# Main_Design.net
KiCad netlist of a schematic drawn in Altium Designer
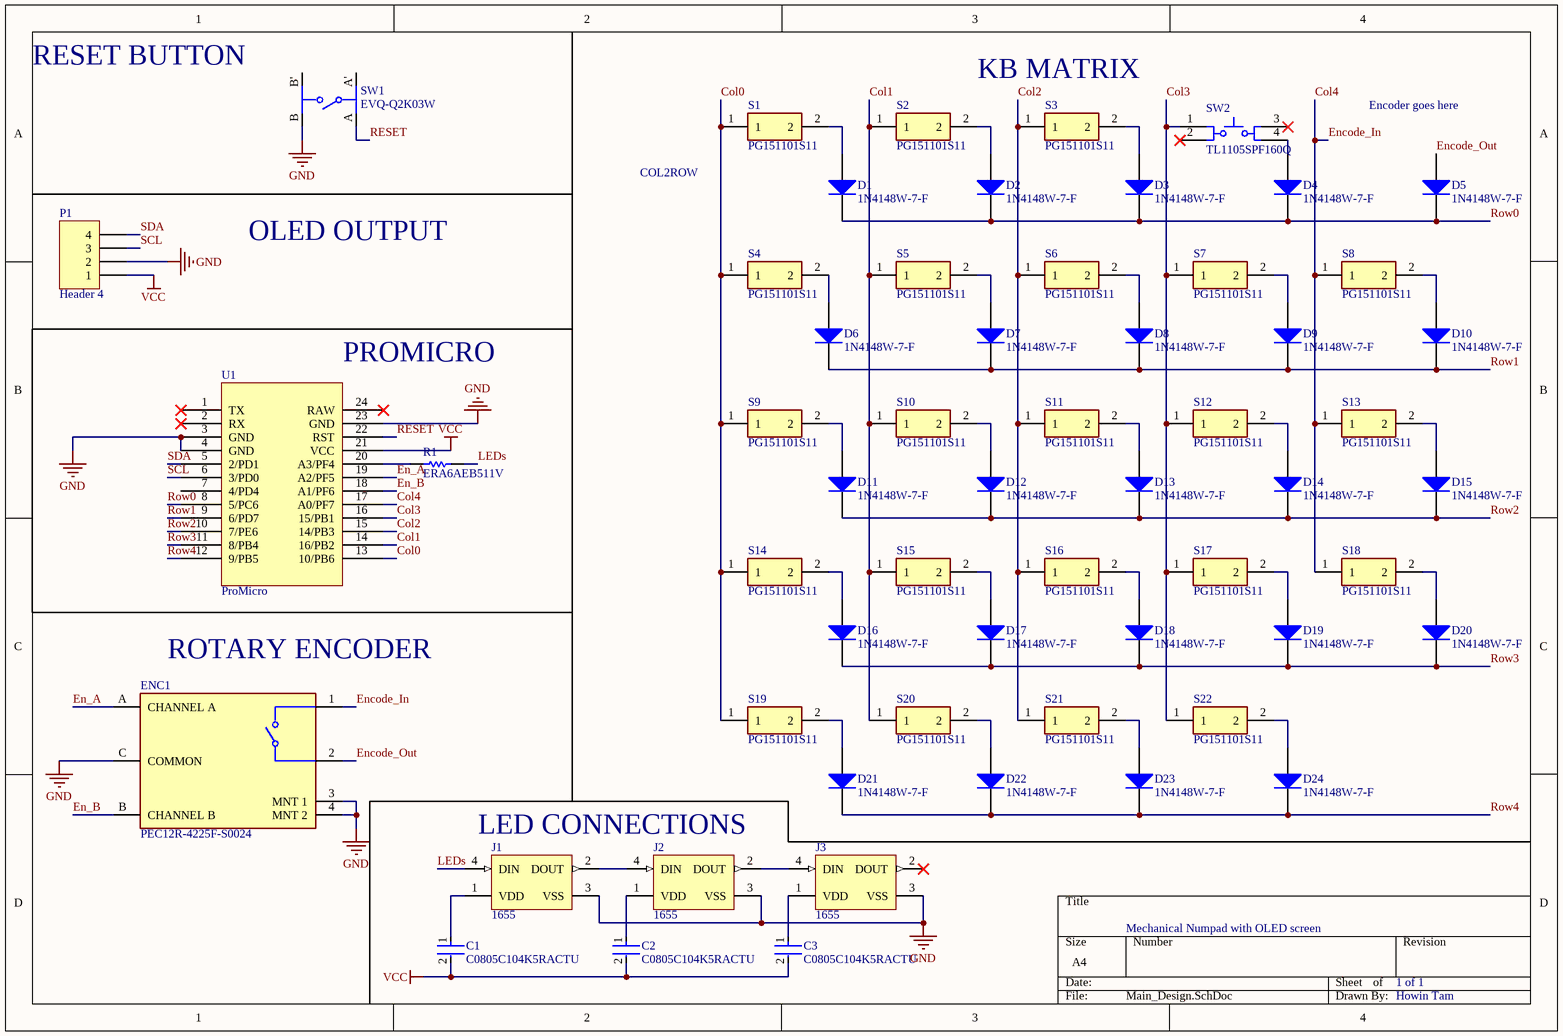
[diagram p0: Main_Design.SchDoc]

(export (version "E")
  (design (tool "Eeschema 10.0.6"))
  (components
    (comp (ref "C1")
      (value "C0805C104K5RACTU")
      (footprint "FP-C0805C-DN-MFG")
      (description "CAP CER 0.1UF 50V X7R 0805")
      (fields
        (field (name "MANUFACTURER") "KEMET")
        (field (name "OCTOPART") "https://octopart.com/c0805c104k5ractu-kemet-143926")
      )
      (libsource (lib "Altium Content Vault") (part "b4654b650e69147ec39a6b967a45e02"))
    )
    (comp (ref "C2")
      (value "C0805C104K5RACTU")
      (footprint "FP-C0805C-DN-MFG")
      (description "CAP CER 0.1UF 50V X7R 0805")
      (fields
        (field (name "MANUFACTURER") "KEMET")
        (field (name "OCTOPART") "https://octopart.com/c0805c104k5ractu-kemet-143926")
      )
      (libsource (lib "Altium Content Vault") (part "b4654b650e69147ec39a6b967a45e02"))
    )
    (comp (ref "C3")
      (value "C0805C104K5RACTU")
      (footprint "FP-C0805C-DN-MFG")
      (description "CAP CER 0.1UF 50V X7R 0805")
      (fields
        (field (name "MANUFACTURER") "KEMET")
        (field (name "OCTOPART") "https://octopart.com/c0805c104k5ractu-kemet-143926")
      )
      (libsource (lib "Altium Content Vault") (part "b4654b650e69147ec39a6b967a45e02"))
    )
    (comp (ref "D1")
      (value "1N4148W-7-F")
      (footprint "DIOD-SOD123-2_V")
      (description "Fast Switching Diode, 100 V, 0.15 A, -65 to 150 degC, 2-Pin?SOD123, RoHS, Tape and Reel")
      (fields (field (name "MANUFACTURER") "DiodesIncorporated"))
      (libsource (lib "Altium Content Vault") (part "D-AK-2"))
    )
    (comp (ref "D2")
      (value "1N4148W-7-F")
      (footprint "DIOD-SOD123-2_V")
      (description "Fast Switching Diode, 100 V, 0.15 A, -65 to 150 degC, 2-Pin?SOD123, RoHS, Tape and Reel")
      (fields (field (name "MANUFACTURER") "DiodesIncorporated"))
      (libsource (lib "Altium Content Vault") (part "D-AK-2"))
    )
    (comp (ref "D3")
      (value "1N4148W-7-F")
      (footprint "DIOD-SOD123-2_V")
      (description "Fast Switching Diode, 100 V, 0.15 A, -65 to 150 degC, 2-Pin?SOD123, RoHS, Tape and Reel")
      (fields (field (name "MANUFACTURER") "DiodesIncorporated"))
      (libsource (lib "Altium Content Vault") (part "D-AK-2"))
    )
    (comp (ref "D4")
      (value "1N4148W-7-F")
      (footprint "DIOD-SOD123-2_V")
      (description "Fast Switching Diode, 100 V, 0.15 A, -65 to 150 degC, 2-Pin?SOD123, RoHS, Tape and Reel")
      (fields (field (name "MANUFACTURER") "DiodesIncorporated"))
      (libsource (lib "Altium Content Vault") (part "D-AK-2"))
    )
    (comp (ref "D5")
      (value "1N4148W-7-F")
      (footprint "DIOD-SOD123-2_V")
      (description "Fast Switching Diode, 100 V, 0.15 A, -65 to 150 degC, 2-Pin?SOD123, RoHS, Tape and Reel")
      (fields (field (name "MANUFACTURER") "DiodesIncorporated"))
      (libsource (lib "Altium Content Vault") (part "D-AK-2"))
    )
    (comp (ref "D6")
      (value "1N4148W-7-F")
      (footprint "DIOD-SOD123-2_V")
      (description "Fast Switching Diode, 100 V, 0.15 A, -65 to 150 degC, 2-Pin?SOD123, RoHS, Tape and Reel")
      (fields (field (name "MANUFACTURER") "DiodesIncorporated"))
      (libsource (lib "Altium Content Vault") (part "D-AK-2"))
    )
    (comp (ref "D7")
      (value "1N4148W-7-F")
      (footprint "DIOD-SOD123-2_V")
      (description "Fast Switching Diode, 100 V, 0.15 A, -65 to 150 degC, 2-Pin?SOD123, RoHS, Tape and Reel")
      (fields (field (name "MANUFACTURER") "DiodesIncorporated"))
      (libsource (lib "Altium Content Vault") (part "D-AK-2"))
    )
    (comp (ref "D8")
      (value "1N4148W-7-F")
      (footprint "DIOD-SOD123-2_V")
      (description "Fast Switching Diode, 100 V, 0.15 A, -65 to 150 degC, 2-Pin?SOD123, RoHS, Tape and Reel")
      (fields (field (name "MANUFACTURER") "DiodesIncorporated"))
      (libsource (lib "Altium Content Vault") (part "D-AK-2"))
    )
    (comp (ref "D9")
      (value "1N4148W-7-F")
      (footprint "DIOD-SOD123-2_V")
      (description "Fast Switching Diode, 100 V, 0.15 A, -65 to 150 degC, 2-Pin?SOD123, RoHS, Tape and Reel")
      (fields (field (name "MANUFACTURER") "DiodesIncorporated"))
      (libsource (lib "Altium Content Vault") (part "D-AK-2"))
    )
    (comp (ref "D10")
      (value "1N4148W-7-F")
      (footprint "DIOD-SOD123-2_V")
      (description "Fast Switching Diode, 100 V, 0.15 A, -65 to 150 degC, 2-Pin?SOD123, RoHS, Tape and Reel")
      (fields (field (name "MANUFACTURER") "DiodesIncorporated"))
      (libsource (lib "Altium Content Vault") (part "D-AK-2"))
    )
    (comp (ref "D11")
      (value "1N4148W-7-F")
      (footprint "DIOD-SOD123-2_V")
      (description "Fast Switching Diode, 100 V, 0.15 A, -65 to 150 degC, 2-Pin?SOD123, RoHS, Tape and Reel")
      (fields (field (name "MANUFACTURER") "DiodesIncorporated"))
      (libsource (lib "Altium Content Vault") (part "D-AK-2"))
    )
    (comp (ref "D12")
      (value "1N4148W-7-F")
      (footprint "DIOD-SOD123-2_V")
      (description "Fast Switching Diode, 100 V, 0.15 A, -65 to 150 degC, 2-Pin?SOD123, RoHS, Tape and Reel")
      (fields (field (name "MANUFACTURER") "DiodesIncorporated"))
      (libsource (lib "Altium Content Vault") (part "D-AK-2"))
    )
    (comp (ref "D13")
      (value "1N4148W-7-F")
      (footprint "DIOD-SOD123-2_V")
      (description "Fast Switching Diode, 100 V, 0.15 A, -65 to 150 degC, 2-Pin?SOD123, RoHS, Tape and Reel")
      (fields (field (name "MANUFACTURER") "DiodesIncorporated"))
      (libsource (lib "Altium Content Vault") (part "D-AK-2"))
    )
    (comp (ref "D14")
      (value "1N4148W-7-F")
      (footprint "DIOD-SOD123-2_V")
      (description "Fast Switching Diode, 100 V, 0.15 A, -65 to 150 degC, 2-Pin?SOD123, RoHS, Tape and Reel")
      (fields (field (name "MANUFACTURER") "DiodesIncorporated"))
      (libsource (lib "Altium Content Vault") (part "D-AK-2"))
    )
    (comp (ref "D15")
      (value "1N4148W-7-F")
      (footprint "DIOD-SOD123-2_V")
      (description "Fast Switching Diode, 100 V, 0.15 A, -65 to 150 degC, 2-Pin?SOD123, RoHS, Tape and Reel")
      (fields (field (name "MANUFACTURER") "DiodesIncorporated"))
      (libsource (lib "Altium Content Vault") (part "D-AK-2"))
    )
    (comp (ref "D16")
      (value "1N4148W-7-F")
      (footprint "DIOD-SOD123-2_V")
      (description "Fast Switching Diode, 100 V, 0.15 A, -65 to 150 degC, 2-Pin?SOD123, RoHS, Tape and Reel")
      (fields (field (name "MANUFACTURER") "DiodesIncorporated"))
      (libsource (lib "Altium Content Vault") (part "D-AK-2"))
    )
    (comp (ref "D17")
      (value "1N4148W-7-F")
      (footprint "DIOD-SOD123-2_V")
      (description "Fast Switching Diode, 100 V, 0.15 A, -65 to 150 degC, 2-Pin?SOD123, RoHS, Tape and Reel")
      (fields (field (name "MANUFACTURER") "DiodesIncorporated"))
      (libsource (lib "Altium Content Vault") (part "D-AK-2"))
    )
    (comp (ref "D18")
      (value "1N4148W-7-F")
      (footprint "DIOD-SOD123-2_V")
      (description "Fast Switching Diode, 100 V, 0.15 A, -65 to 150 degC, 2-Pin?SOD123, RoHS, Tape and Reel")
      (fields (field (name "MANUFACTURER") "DiodesIncorporated"))
      (libsource (lib "Altium Content Vault") (part "D-AK-2"))
    )
    (comp (ref "D19")
      (value "1N4148W-7-F")
      (footprint "DIOD-SOD123-2_V")
      (description "Fast Switching Diode, 100 V, 0.15 A, -65 to 150 degC, 2-Pin?SOD123, RoHS, Tape and Reel")
      (fields (field (name "MANUFACTURER") "DiodesIncorporated"))
      (libsource (lib "Altium Content Vault") (part "D-AK-2"))
    )
    (comp (ref "D20")
      (value "1N4148W-7-F")
      (footprint "DIOD-SOD123-2_V")
      (description "Fast Switching Diode, 100 V, 0.15 A, -65 to 150 degC, 2-Pin?SOD123, RoHS, Tape and Reel")
      (fields (field (name "MANUFACTURER") "DiodesIncorporated"))
      (libsource (lib "Altium Content Vault") (part "D-AK-2"))
    )
    (comp (ref "D21")
      (value "1N4148W-7-F")
      (footprint "DIOD-SOD123-2_V")
      (description "Fast Switching Diode, 100 V, 0.15 A, -65 to 150 degC, 2-Pin?SOD123, RoHS, Tape and Reel")
      (fields (field (name "MANUFACTURER") "DiodesIncorporated"))
      (libsource (lib "Altium Content Vault") (part "D-AK-2"))
    )
    (comp (ref "D22")
      (value "1N4148W-7-F")
      (footprint "DIOD-SOD123-2_V")
      (description "Fast Switching Diode, 100 V, 0.15 A, -65 to 150 degC, 2-Pin?SOD123, RoHS, Tape and Reel")
      (fields (field (name "MANUFACTURER") "DiodesIncorporated"))
      (libsource (lib "Altium Content Vault") (part "D-AK-2"))
    )
    (comp (ref "D23")
      (value "1N4148W-7-F")
      (footprint "DIOD-SOD123-2_V")
      (description "Fast Switching Diode, 100 V, 0.15 A, -65 to 150 degC, 2-Pin?SOD123, RoHS, Tape and Reel")
      (fields (field (name "MANUFACTURER") "DiodesIncorporated"))
      (libsource (lib "Altium Content Vault") (part "D-AK-2"))
    )
    (comp (ref "D24")
      (value "1N4148W-7-F")
      (footprint "DIOD-SOD123-2_V")
      (description "Fast Switching Diode, 100 V, 0.15 A, -65 to 150 degC, 2-Pin?SOD123, RoHS, Tape and Reel")
      (fields (field (name "MANUFACTURER") "DiodesIncorporated"))
      (libsource (lib "Altium Content Vault") (part "D-AK-2"))
    )
    (comp (ref "ENC1")
      (value "PEC12R-4225F-S0024")
      (footprint "FP-PEC12R-4225F-S0024-MFG")
      (description "ROTARY ENCODER MECHANICAL 24PPR")
      (libsource (lib "Altium Content Vault") (part "084942c7348c54a7e5fe2df5ed54478"))
    )
    (comp (ref "J1")
      (value "1655")
      (footprint "ADA-RGB-1655_V")
      (fields (field (name "MANUFACTURER") "Adafruit-Industries-LLC"))
      (libsource (lib "Altium Content Vault") (part "ADA-RGB-1655-4"))
    )
    (comp (ref "J2")
      (value "1655")
      (footprint "ADA-RGB-1655_V")
      (fields (field (name "MANUFACTURER") "Adafruit-Industries-LLC"))
      (libsource (lib "Altium Content Vault") (part "ADA-RGB-1655-4"))
    )
    (comp (ref "J3")
      (value "1655")
      (footprint "ADA-RGB-1655_V")
      (fields (field (name "MANUFACTURER") "Adafruit-Industries-LLC"))
      (libsource (lib "Altium Content Vault") (part "ADA-RGB-1655-4"))
    )
    (comp (ref "P1")
      (value "Header 4")
      (footprint "HDR1X4")
      (description "Header, 4-Pin")
      (fields (field (name "PUBLISHER") "Altium Limited"))
      (libsource (lib "Miscellaneous Connectors") (part "Header 4"))
    )
    (comp (ref "R1")
      (value "ERA6AEB511V")
      (footprint "RESC2013X60X40ML20T25")
      (fields (field (name "MANUFACTURER") "Panasonic"))
      (libsource (lib "Altium Content Vault") (part "RES"))
    )
    (comp (ref "S1")
      (value "PG151101S11")
      (footprint "SW_PG151101S11")
      (description "Keyswitch")
      (fields (field (name "MF") "Kailh"))
      (libsource (lib "PG151101S11") (part "PG151101S11"))
    )
    (comp (ref "S2")
      (value "PG151101S11")
      (footprint "SW_PG151101S11")
      (description "Keyswitch")
      (fields (field (name "MF") "Kailh"))
      (libsource (lib "PG151101S11") (part "PG151101S11"))
    )
    (comp (ref "S3")
      (value "PG151101S11")
      (footprint "SW_PG151101S11")
      (description "Keyswitch")
      (fields (field (name "MF") "Kailh"))
      (libsource (lib "PG151101S11") (part "PG151101S11"))
    )
    (comp (ref "S4")
      (value "PG151101S11")
      (footprint "SW_PG151101S11")
      (description "Keyswitch")
      (fields (field (name "MF") "Kailh"))
      (libsource (lib "PG151101S11") (part "PG151101S11"))
    )
    (comp (ref "S5")
      (value "PG151101S11")
      (footprint "SW_PG151101S11")
      (description "Keyswitch")
      (fields (field (name "MF") "Kailh"))
      (libsource (lib "PG151101S11") (part "PG151101S11"))
    )
    (comp (ref "S6")
      (value "PG151101S11")
      (footprint "SW_PG151101S11")
      (description "Keyswitch")
      (fields (field (name "MF") "Kailh"))
      (libsource (lib "PG151101S11") (part "PG151101S11"))
    )
    (comp (ref "S7")
      (value "PG151101S11")
      (footprint "SW_PG151101S11")
      (description "Keyswitch")
      (fields (field (name "MF") "Kailh"))
      (libsource (lib "PG151101S11") (part "PG151101S11"))
    )
    (comp (ref "S8")
      (value "PG151101S11")
      (footprint "SW_PG151101S11")
      (description "Keyswitch")
      (fields (field (name "MF") "Kailh"))
      (libsource (lib "PG151101S11") (part "PG151101S11"))
    )
    (comp (ref "S9")
      (value "PG151101S11")
      (footprint "SW_PG151101S11")
      (description "Keyswitch")
      (fields (field (name "MF") "Kailh"))
      (libsource (lib "PG151101S11") (part "PG151101S11"))
    )
    (comp (ref "S10")
      (value "PG151101S11")
      (footprint "SW_PG151101S11")
      (description "Keyswitch")
      (fields (field (name "MF") "Kailh"))
      (libsource (lib "PG151101S11") (part "PG151101S11"))
    )
    (comp (ref "S11")
      (value "PG151101S11")
      (footprint "SW_PG151101S11")
      (description "Keyswitch")
      (fields (field (name "MF") "Kailh"))
      (libsource (lib "PG151101S11") (part "PG151101S11"))
    )
    (comp (ref "S12")
      (value "PG151101S11")
      (footprint "SW_PG151101S11")
      (description "Keyswitch")
      (fields (field (name "MF") "Kailh"))
      (libsource (lib "PG151101S11") (part "PG151101S11"))
    )
    (comp (ref "S13")
      (value "PG151101S11")
      (footprint "SW_PG151101S11")
      (description "Keyswitch")
      (fields (field (name "MF") "Kailh"))
      (libsource (lib "PG151101S11") (part "PG151101S11"))
    )
    (comp (ref "S14")
      (value "PG151101S11")
      (footprint "SW_PG151101S11")
      (description "Keyswitch")
      (fields (field (name "MF") "Kailh"))
      (libsource (lib "PG151101S11") (part "PG151101S11"))
    )
    (comp (ref "S15")
      (value "PG151101S11")
      (footprint "SW_PG151101S11")
      (description "Keyswitch")
      (fields (field (name "MF") "Kailh"))
      (libsource (lib "PG151101S11") (part "PG151101S11"))
    )
    (comp (ref "S16")
      (value "PG151101S11")
      (footprint "SW_PG151101S11")
      (description "Keyswitch")
      (fields (field (name "MF") "Kailh"))
      (libsource (lib "PG151101S11") (part "PG151101S11"))
    )
    (comp (ref "S17")
      (value "PG151101S11")
      (footprint "SW_PG151101S11")
      (description "Keyswitch")
      (fields (field (name "MF") "Kailh"))
      (libsource (lib "PG151101S11") (part "PG151101S11"))
    )
    (comp (ref "S18")
      (value "PG151101S11")
      (footprint "SW_PG151101S11")
      (description "Keyswitch")
      (fields (field (name "MF") "Kailh"))
      (libsource (lib "PG151101S11") (part "PG151101S11"))
    )
    (comp (ref "S19")
      (value "PG151101S11")
      (footprint "SW_PG151101S11")
      (description "Keyswitch")
      (fields (field (name "MF") "Kailh"))
      (libsource (lib "PG151101S11") (part "PG151101S11"))
    )
    (comp (ref "S20")
      (value "PG151101S11")
      (footprint "SW_PG151101S11")
      (description "Keyswitch")
      (fields (field (name "MF") "Kailh"))
      (libsource (lib "PG151101S11") (part "PG151101S11"))
    )
    (comp (ref "S21")
      (value "PG151101S11")
      (footprint "SW_PG151101S11")
      (description "Keyswitch")
      (fields (field (name "MF") "Kailh"))
      (libsource (lib "PG151101S11") (part "PG151101S11"))
    )
    (comp (ref "S22")
      (value "PG151101S11")
      (footprint "SW_PG151101S11")
      (description "Keyswitch")
      (fields (field (name "MF") "Kailh"))
      (libsource (lib "PG151101S11") (part "PG151101S11"))
    )
    (comp (ref "SW1")
      (value "EVQ-Q2K03W")
      (footprint "FP-EVQ-Q2K03W-MFG")
      (description "SWITCH TACTILE SPST-NO 0.02A 15V")
      (fields
        (field (name "MANUFACTURER") "Panasonic Electronic Components")
        (field (name "OCTOPART") "https://octopart.com/evq-q2k03w-panasonic-1224370")
      )
      (libsource (lib "Altium Content Vault") (part "9677229990528492022b31d4503349f"))
    )
    (comp (ref "SW2")
      (value "TL1105SPF160Q")
      (footprint "ESWI-TL1105SPF_V")
      (description "Tact Switch, SPST-NO, 50 mA, 12 VDC, -20 to 70 degC, 4-Pin THD, RoHS, Bulk")
      (fields (field (name "MANUFACTURER") "E-Switch"))
      (libsource (lib "Altium Content Vault") (part "SW-SPST-NO-4"))
    )
    (comp (ref "U1")
      (value "ProMicro")
      (footprint "PCBComponent_1")
      (libsource (lib "ProMicro") (part "Component_1"))
    )
  )
  (nets
    (net (code "1") (name "/Col0") (class "Default")
      (node (ref "S1") (pin "1") (pinfunction "1_1") (pintype "passive"))
      (node (ref "S14") (pin "1") (pinfunction "1_1") (pintype "passive"))
      (node (ref "S19") (pin "1") (pinfunction "1_1") (pintype "passive"))
      (node (ref "S4") (pin "1") (pinfunction "1_1") (pintype "passive"))
      (node (ref "S9") (pin "1") (pinfunction "1_1") (pintype "passive"))
      (node (ref "U1") (pin "13") (pinfunction "10/PB6_13") (pintype "passive"))
    )
    (net (code "2") (name "/Col1") (class "Default")
      (node (ref "S10") (pin "1") (pinfunction "1_1") (pintype "passive"))
      (node (ref "S15") (pin "1") (pinfunction "1_1") (pintype "passive"))
      (node (ref "S2") (pin "1") (pinfunction "1_1") (pintype "passive"))
      (node (ref "S20") (pin "1") (pinfunction "1_1") (pintype "passive"))
      (node (ref "S5") (pin "1") (pinfunction "1_1") (pintype "passive"))
      (node (ref "U1") (pin "14") (pinfunction "16/PB2_14") (pintype "passive"))
    )
    (net (code "3") (name "/Col2") (class "Default")
      (node (ref "S11") (pin "1") (pinfunction "1_1") (pintype "passive"))
      (node (ref "S16") (pin "1") (pinfunction "1_1") (pintype "passive"))
      (node (ref "S21") (pin "1") (pinfunction "1_1") (pintype "passive"))
      (node (ref "S3") (pin "1") (pinfunction "1_1") (pintype "passive"))
      (node (ref "S6") (pin "1") (pinfunction "1_1") (pintype "passive"))
      (node (ref "U1") (pin "15") (pinfunction "14/PB3_15") (pintype "passive"))
    )
    (net (code "4") (name "/Col3") (class "Default")
      (node (ref "S12") (pin "1") (pinfunction "1_1") (pintype "passive"))
      (node (ref "S17") (pin "1") (pinfunction "1_1") (pintype "passive"))
      (node (ref "S22") (pin "1") (pinfunction "1_1") (pintype "passive"))
      (node (ref "S7") (pin "1") (pinfunction "1_1") (pintype "passive"))
      (node (ref "SW2") (pin "1") (pinfunction "1_1") (pintype "passive"))
      (node (ref "U1") (pin "16") (pinfunction "15/PB1_16") (pintype "passive"))
    )
    (net (code "5") (name "/Col4") (class "Default")
      (node (ref "ENC1") (pin "1") (pinfunction "1_1") (pintype "passive"))
      (node (ref "S13") (pin "1") (pinfunction "1_1") (pintype "passive"))
      (node (ref "S18") (pin "1") (pinfunction "1_1") (pintype "passive"))
      (node (ref "S8") (pin "1") (pinfunction "1_1") (pintype "passive"))
      (node (ref "U1") (pin "17") (pinfunction "A0/PF7_17") (pintype "passive"))
    )
    (net (code "6") (name "/En_A") (class "Default")
      (node (ref "ENC1") (pin "A") (pinfunction "CHANNEL_A_A") (pintype "passive"))
      (node (ref "U1") (pin "19") (pinfunction "A2/PF5_19") (pintype "passive"))
    )
    (net (code "7") (name "/En_B") (class "Default")
      (node (ref "ENC1") (pin "B") (pinfunction "CHANNEL_B_B") (pintype "passive"))
      (node (ref "U1") (pin "18") (pinfunction "A1/PF6_18") (pintype "passive"))
    )
    (net (code "8") (name "/Encode_Out") (class "Default")
      (node (ref "D5") (pin "1") (pinfunction "A_1") (pintype "passive"))
      (node (ref "ENC1") (pin "2") (pinfunction "2_2") (pintype "passive"))
    )
    (net (code "9") (name "/LEDs") (class "Default")
      (node (ref "J1") (pin "4") (pinfunction "DIN_4") (pintype "input"))
      (node (ref "R1") (pin "2") (pinfunction "2_2") (pintype "passive"))
    )
    (net (code "10") (name "/RESET") (class "Default")
      (node (ref "SW1") (pin "A") (pinfunction "A_A") (pintype "passive"))
      (node (ref "U1") (pin "22") (pinfunction "RST_22") (pintype "passive"))
    )
    (net (code "11") (name "/Row0") (class "Default")
      (node (ref "D1") (pin "2") (pinfunction "K_2") (pintype "passive"))
      (node (ref "D2") (pin "2") (pinfunction "K_2") (pintype "passive"))
      (node (ref "D3") (pin "2") (pinfunction "K_2") (pintype "passive"))
      (node (ref "D4") (pin "2") (pinfunction "K_2") (pintype "passive"))
      (node (ref "D5") (pin "2") (pinfunction "K_2") (pintype "passive"))
      (node (ref "U1") (pin "8") (pinfunction "5/PC6_8") (pintype "passive"))
    )
    (net (code "12") (name "/Row1") (class "Default")
      (node (ref "D10") (pin "2") (pinfunction "K_2") (pintype "passive"))
      (node (ref "D6") (pin "2") (pinfunction "K_2") (pintype "passive"))
      (node (ref "D7") (pin "2") (pinfunction "K_2") (pintype "passive"))
      (node (ref "D8") (pin "2") (pinfunction "K_2") (pintype "passive"))
      (node (ref "D9") (pin "2") (pinfunction "K_2") (pintype "passive"))
      (node (ref "U1") (pin "9") (pinfunction "6/PD7_9") (pintype "passive"))
    )
    (net (code "13") (name "/Row2") (class "Default")
      (node (ref "D11") (pin "2") (pinfunction "K_2") (pintype "passive"))
      (node (ref "D12") (pin "2") (pinfunction "K_2") (pintype "passive"))
      (node (ref "D13") (pin "2") (pinfunction "K_2") (pintype "passive"))
      (node (ref "D14") (pin "2") (pinfunction "K_2") (pintype "passive"))
      (node (ref "D15") (pin "2") (pinfunction "K_2") (pintype "passive"))
      (node (ref "U1") (pin "10") (pinfunction "7/PE6_10") (pintype "passive"))
    )
    (net (code "14") (name "/Row3") (class "Default")
      (node (ref "D16") (pin "2") (pinfunction "K_2") (pintype "passive"))
      (node (ref "D17") (pin "2") (pinfunction "K_2") (pintype "passive"))
      (node (ref "D18") (pin "2") (pinfunction "K_2") (pintype "passive"))
      (node (ref "D19") (pin "2") (pinfunction "K_2") (pintype "passive"))
      (node (ref "D20") (pin "2") (pinfunction "K_2") (pintype "passive"))
      (node (ref "U1") (pin "11") (pinfunction "8/PB4_11") (pintype "passive"))
    )
    (net (code "15") (name "/Row4") (class "Default")
      (node (ref "D21") (pin "2") (pinfunction "K_2") (pintype "passive"))
      (node (ref "D22") (pin "2") (pinfunction "K_2") (pintype "passive"))
      (node (ref "D23") (pin "2") (pinfunction "K_2") (pintype "passive"))
      (node (ref "D24") (pin "2") (pinfunction "K_2") (pintype "passive"))
      (node (ref "U1") (pin "12") (pinfunction "9/PB5_12") (pintype "passive"))
    )
    (net (code "16") (name "/SCL") (class "Default")
      (node (ref "P1") (pin "3") (pinfunction "3_3") (pintype "passive"))
      (node (ref "U1") (pin "6") (pinfunction "3/PD0_6") (pintype "passive"))
    )
    (net (code "17") (name "/SDA") (class "Default")
      (node (ref "P1") (pin "4") (pinfunction "4_4") (pintype "passive"))
      (node (ref "U1") (pin "5") (pinfunction "2/PD1_5") (pintype "passive"))
    )
    (net (code "18") (name "GND") (class "Default")
      (node (ref "ENC1") (pin "3") (pinfunction "MNT_1_3") (pintype "passive"))
      (node (ref "ENC1") (pin "4") (pinfunction "MNT_2_4") (pintype "passive"))
      (node (ref "ENC1") (pin "C") (pinfunction "COMMON_C") (pintype "passive"))
      (node (ref "J1") (pin "3") (pinfunction "VSS_3") (pintype "power_in"))
      (node (ref "J2") (pin "3") (pinfunction "VSS_3") (pintype "power_in"))
      (node (ref "J3") (pin "3") (pinfunction "VSS_3") (pintype "power_in"))
      (node (ref "P1") (pin "2") (pinfunction "2_2") (pintype "passive"))
      (node (ref "SW1") (pin "B") (pinfunction "B_B") (pintype "passive"))
      (node (ref "U1") (pin "23") (pinfunction "GND_23") (pintype "passive"))
      (node (ref "U1") (pin "3") (pinfunction "GND_3") (pintype "passive"))
      (node (ref "U1") (pin "4") (pinfunction "GND_4") (pintype "passive"))
    )
    (net (code "19") (name "Net-(D1-A)") (class "Default")
      (node (ref "D1") (pin "1") (pinfunction "A_1") (pintype "passive"))
      (node (ref "S1") (pin "2") (pinfunction "2_2") (pintype "passive"))
    )
    (net (code "20") (name "Net-(D2-A)") (class "Default")
      (node (ref "D2") (pin "1") (pinfunction "A_1") (pintype "passive"))
      (node (ref "S2") (pin "2") (pinfunction "2_2") (pintype "passive"))
    )
    (net (code "21") (name "Net-(D3-A)") (class "Default")
      (node (ref "D3") (pin "1") (pinfunction "A_1") (pintype "passive"))
      (node (ref "S3") (pin "2") (pinfunction "2_2") (pintype "passive"))
    )
    (net (code "22") (name "Net-(D4-A)") (class "Default")
      (node (ref "D4") (pin "1") (pinfunction "A_1") (pintype "passive"))
      (node (ref "SW2") (pin "4") (pinfunction "4_4") (pintype "passive"))
    )
    (net (code "23") (name "Net-(D6-A)") (class "Default")
      (node (ref "D6") (pin "1") (pinfunction "A_1") (pintype "passive"))
      (node (ref "S4") (pin "2") (pinfunction "2_2") (pintype "passive"))
    )
    (net (code "24") (name "Net-(D7-A)") (class "Default")
      (node (ref "D7") (pin "1") (pinfunction "A_1") (pintype "passive"))
      (node (ref "S5") (pin "2") (pinfunction "2_2") (pintype "passive"))
    )
    (net (code "25") (name "Net-(D8-A)") (class "Default")
      (node (ref "D8") (pin "1") (pinfunction "A_1") (pintype "passive"))
      (node (ref "S6") (pin "2") (pinfunction "2_2") (pintype "passive"))
    )
    (net (code "26") (name "Net-(D9-A)") (class "Default")
      (node (ref "D9") (pin "1") (pinfunction "A_1") (pintype "passive"))
      (node (ref "S7") (pin "2") (pinfunction "2_2") (pintype "passive"))
    )
    (net (code "27") (name "Net-(D10-A)") (class "Default")
      (node (ref "D10") (pin "1") (pinfunction "A_1") (pintype "passive"))
      (node (ref "S8") (pin "2") (pinfunction "2_2") (pintype "passive"))
    )
    (net (code "28") (name "Net-(D11-A)") (class "Default")
      (node (ref "D11") (pin "1") (pinfunction "A_1") (pintype "passive"))
      (node (ref "S9") (pin "2") (pinfunction "2_2") (pintype "passive"))
    )
    (net (code "29") (name "Net-(D12-A)") (class "Default")
      (node (ref "D12") (pin "1") (pinfunction "A_1") (pintype "passive"))
      (node (ref "S10") (pin "2") (pinfunction "2_2") (pintype "passive"))
    )
    (net (code "30") (name "Net-(D13-A)") (class "Default")
      (node (ref "D13") (pin "1") (pinfunction "A_1") (pintype "passive"))
      (node (ref "S11") (pin "2") (pinfunction "2_2") (pintype "passive"))
    )
    (net (code "31") (name "Net-(D14-A)") (class "Default")
      (node (ref "D14") (pin "1") (pinfunction "A_1") (pintype "passive"))
      (node (ref "S12") (pin "2") (pinfunction "2_2") (pintype "passive"))
    )
    (net (code "32") (name "Net-(D15-A)") (class "Default")
      (node (ref "D15") (pin "1") (pinfunction "A_1") (pintype "passive"))
      (node (ref "S13") (pin "2") (pinfunction "2_2") (pintype "passive"))
    )
    (net (code "33") (name "Net-(D16-A)") (class "Default")
      (node (ref "D16") (pin "1") (pinfunction "A_1") (pintype "passive"))
      (node (ref "S14") (pin "2") (pinfunction "2_2") (pintype "passive"))
    )
    (net (code "34") (name "Net-(D17-A)") (class "Default")
      (node (ref "D17") (pin "1") (pinfunction "A_1") (pintype "passive"))
      (node (ref "S15") (pin "2") (pinfunction "2_2") (pintype "passive"))
    )
    (net (code "35") (name "Net-(D18-A)") (class "Default")
      (node (ref "D18") (pin "1") (pinfunction "A_1") (pintype "passive"))
      (node (ref "S16") (pin "2") (pinfunction "2_2") (pintype "passive"))
    )
    (net (code "36") (name "Net-(D19-A)") (class "Default")
      (node (ref "D19") (pin "1") (pinfunction "A_1") (pintype "passive"))
      (node (ref "S17") (pin "2") (pinfunction "2_2") (pintype "passive"))
    )
    (net (code "37") (name "Net-(D20-A)") (class "Default")
      (node (ref "D20") (pin "1") (pinfunction "A_1") (pintype "passive"))
      (node (ref "S18") (pin "2") (pinfunction "2_2") (pintype "passive"))
    )
    (net (code "38") (name "Net-(D21-A)") (class "Default")
      (node (ref "D21") (pin "1") (pinfunction "A_1") (pintype "passive"))
      (node (ref "S19") (pin "2") (pinfunction "2_2") (pintype "passive"))
    )
    (net (code "39") (name "Net-(D22-A)") (class "Default")
      (node (ref "D22") (pin "1") (pinfunction "A_1") (pintype "passive"))
      (node (ref "S20") (pin "2") (pinfunction "2_2") (pintype "passive"))
    )
    (net (code "40") (name "Net-(D23-A)") (class "Default")
      (node (ref "D23") (pin "1") (pinfunction "A_1") (pintype "passive"))
      (node (ref "S21") (pin "2") (pinfunction "2_2") (pintype "passive"))
    )
    (net (code "41") (name "Net-(D24-A)") (class "Default")
      (node (ref "D24") (pin "1") (pinfunction "A_1") (pintype "passive"))
      (node (ref "S22") (pin "2") (pinfunction "2_2") (pintype "passive"))
    )
    (net (code "42") (name "Net-(J1-DOUT)") (class "Default")
      (node (ref "J1") (pin "2") (pinfunction "DOUT_2") (pintype "output"))
      (node (ref "J2") (pin "4") (pinfunction "DIN_4") (pintype "input"))
    )
    (net (code "43") (name "Net-(J1-VDD)") (class "Default")
      (node (ref "C1") (pin "1") (pinfunction "1_1") (pintype "passive"))
      (node (ref "J1") (pin "1") (pinfunction "VDD_1") (pintype "power_in"))
    )
    (net (code "44") (name "Net-(J2-DOUT)") (class "Default")
      (node (ref "J2") (pin "2") (pinfunction "DOUT_2") (pintype "output"))
      (node (ref "J3") (pin "4") (pinfunction "DIN_4") (pintype "input"))
    )
    (net (code "45") (name "Net-(J2-VDD)") (class "Default")
      (node (ref "C2") (pin "1") (pinfunction "1_1") (pintype "passive"))
      (node (ref "J2") (pin "1") (pinfunction "VDD_1") (pintype "power_in"))
    )
    (net (code "46") (name "Net-(J3-VDD)") (class "Default")
      (node (ref "C3") (pin "1") (pinfunction "1_1") (pintype "passive"))
      (node (ref "J3") (pin "1") (pinfunction "VDD_1") (pintype "power_in"))
    )
    (net (code "47") (name "Net-(U1-A3{slash}PF4)") (class "Default")
      (node (ref "R1") (pin "1") (pinfunction "1_1") (pintype "passive"))
      (node (ref "U1") (pin "20") (pinfunction "A3/PF4_20") (pintype "passive"))
    )
    (net (code "48") (name "VCC") (class "Default")
      (node (ref "C1") (pin "2") (pinfunction "2_2") (pintype "passive"))
      (node (ref "C2") (pin "2") (pinfunction "2_2") (pintype "passive"))
      (node (ref "C3") (pin "2") (pinfunction "2_2") (pintype "passive"))
      (node (ref "P1") (pin "1") (pinfunction "1_1") (pintype "passive"))
      (node (ref "U1") (pin "21") (pinfunction "VCC_21") (pintype "passive"))
    )
    (net (code "49") (name "unconnected-(J3-DOUT-Pad2)") (class "Default")
      (node (ref "J3") (pin "2") (pinfunction "DOUT_2") (pintype "output+no_connect"))
    )
    (net (code "50") (name "unconnected-(SW1-PadA')") (class "Default")
      (node (ref "SW1") (pin "A'") (pinfunction "A'_A'") (pintype "passive"))
    )
    (net (code "51") (name "unconnected-(SW1-PadB')") (class "Default")
      (node (ref "SW1") (pin "B'") (pinfunction "B'_B'") (pintype "passive"))
    )
    (net (code "52") (name "unconnected-(SW2-Pad2)") (class "Default")
      (node (ref "SW2") (pin "2") (pinfunction "2_2") (pintype "passive+no_connect"))
    )
    (net (code "53") (name "unconnected-(SW2-Pad3)") (class "Default")
      (node (ref "SW2") (pin "3") (pinfunction "3_3") (pintype "passive+no_connect"))
    )
    (net (code "54") (name "unconnected-(U1-4{slash}PD4-Pad7)") (class "Default")
      (node (ref "U1") (pin "7") (pinfunction "4/PD4_7") (pintype "passive"))
    )
    (net (code "55") (name "unconnected-(U1-RAW-Pad24)") (class "Default")
      (node (ref "U1") (pin "24") (pinfunction "RAW_24") (pintype "passive+no_connect"))
    )
    (net (code "56") (name "unconnected-(U1-RX-Pad2)") (class "Default")
      (node (ref "U1") (pin "2") (pinfunction "RX_2") (pintype "passive+no_connect"))
    )
    (net (code "57") (name "unconnected-(U1-TX-Pad1)") (class "Default")
      (node (ref "U1") (pin "1") (pinfunction "TX_1") (pintype "passive+no_connect"))
    )
  )
)
